# lv_controller_motor_drivers.net
KiCad netlist of a schematic drawn in Altium Designer
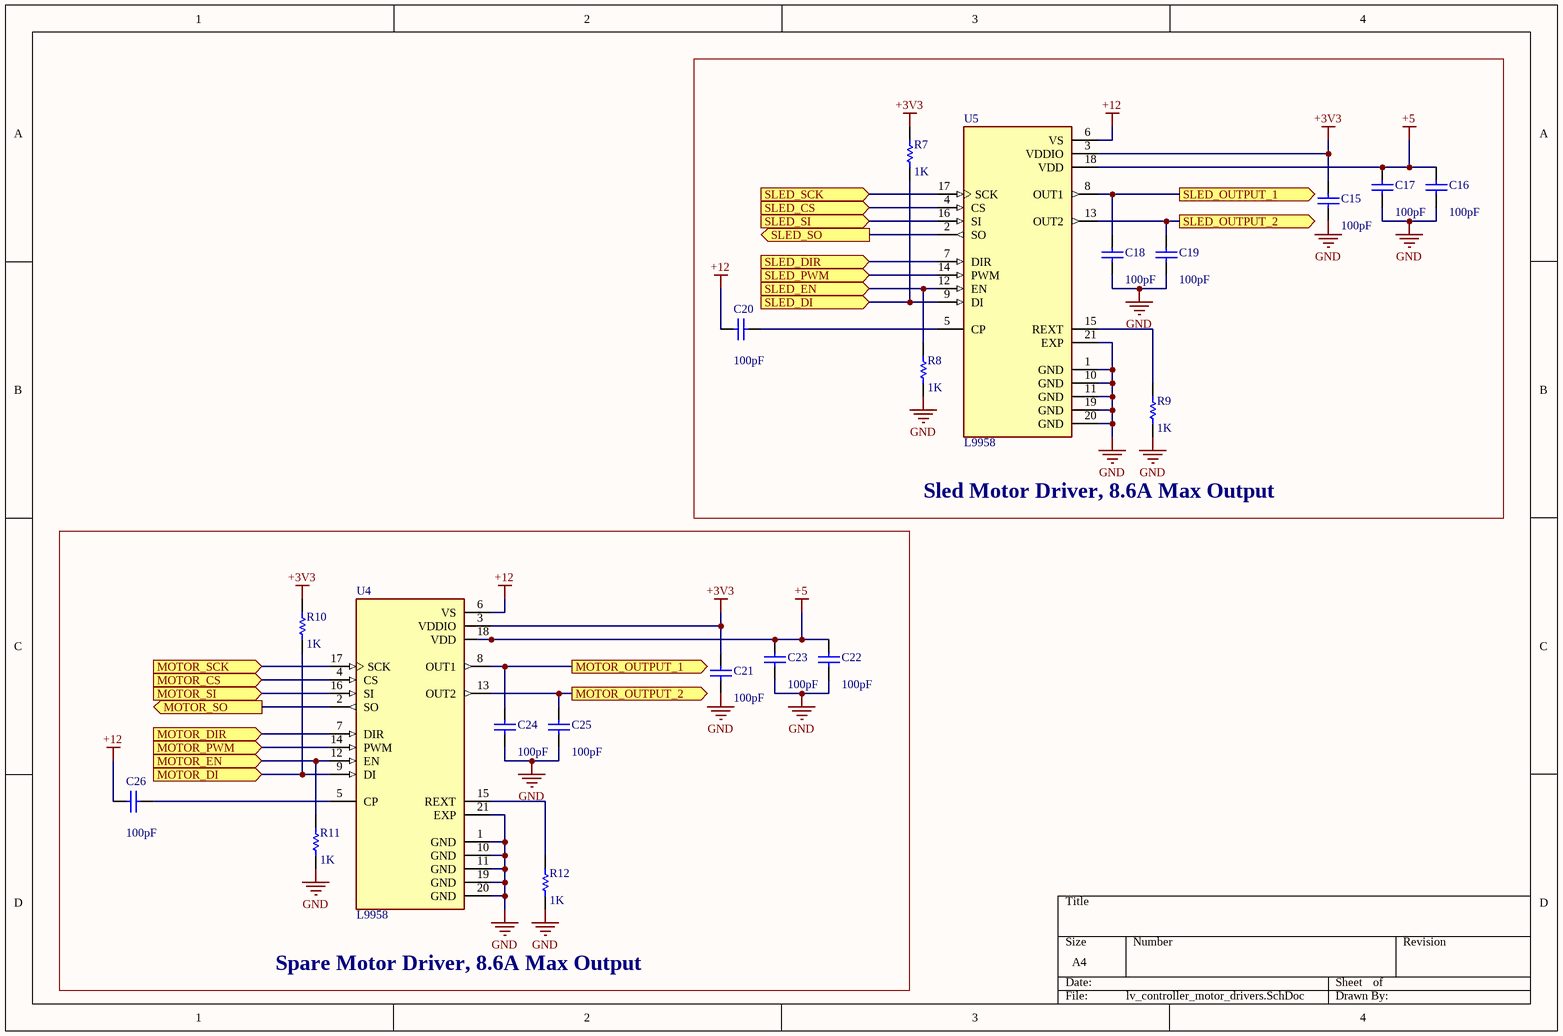
[diagram p0: lv_controller_motor_drivers.SchDoc]

(export (version "E")
  (design (tool "Eeschema 10.0.6"))
  (components
    (comp (ref "C15")
      (value "100pF")
      (footprint "C0805")
      (description "Capacitor")
      (fields (field (name "Comment") "Cap") (field (name "PUBLISHER") "Altium Limited"))
      (libsource (lib "Miscellaneous Devices") (part "Cap"))
    )
    (comp (ref "C16")
      (value "100pF")
      (footprint "C0805")
      (description "Capacitor")
      (fields (field (name "Comment") "Cap") (field (name "PUBLISHER") "Altium Limited"))
      (libsource (lib "Miscellaneous Devices") (part "Cap"))
    )
    (comp (ref "C17")
      (value "100pF")
      (footprint "C0805")
      (description "Capacitor")
      (fields (field (name "Comment") "Cap") (field (name "PUBLISHER") "Altium Limited"))
      (libsource (lib "Miscellaneous Devices") (part "Cap"))
    )
    (comp (ref "C18")
      (value "100pF")
      (footprint "C0805")
      (description "Capacitor")
      (fields (field (name "Comment") "Cap") (field (name "PUBLISHER") "Altium Limited"))
      (libsource (lib "Miscellaneous Devices") (part "Cap"))
    )
    (comp (ref "C19")
      (value "100pF")
      (footprint "C0805")
      (description "Capacitor")
      (fields (field (name "Comment") "Cap") (field (name "PUBLISHER") "Altium Limited"))
      (libsource (lib "Miscellaneous Devices") (part "Cap"))
    )
    (comp (ref "C20")
      (value "100pF")
      (footprint "C0805")
      (description "Capacitor")
      (fields (field (name "Comment") "Cap") (field (name "PUBLISHER") "Altium Limited"))
      (libsource (lib "Miscellaneous Devices") (part "Cap"))
    )
    (comp (ref "C21")
      (value "100pF")
      (footprint "C0805")
      (description "Capacitor")
      (fields (field (name "Comment") "Cap") (field (name "PUBLISHER") "Altium Limited"))
      (libsource (lib "Miscellaneous Devices") (part "Cap"))
    )
    (comp (ref "C22")
      (value "100pF")
      (footprint "C0805")
      (description "Capacitor")
      (fields (field (name "Comment") "Cap") (field (name "PUBLISHER") "Altium Limited"))
      (libsource (lib "Miscellaneous Devices") (part "Cap"))
    )
    (comp (ref "C23")
      (value "100pF")
      (footprint "C0805")
      (description "Capacitor")
      (fields (field (name "Comment") "Cap") (field (name "PUBLISHER") "Altium Limited"))
      (libsource (lib "Miscellaneous Devices") (part "Cap"))
    )
    (comp (ref "C24")
      (value "100pF")
      (footprint "C0805")
      (description "Capacitor")
      (fields (field (name "Comment") "Cap") (field (name "PUBLISHER") "Altium Limited"))
      (libsource (lib "Miscellaneous Devices") (part "Cap"))
    )
    (comp (ref "C25")
      (value "100pF")
      (footprint "C0805")
      (description "Capacitor")
      (fields (field (name "Comment") "Cap") (field (name "PUBLISHER") "Altium Limited"))
      (libsource (lib "Miscellaneous Devices") (part "Cap"))
    )
    (comp (ref "C26")
      (value "100pF")
      (footprint "C0805")
      (description "Capacitor")
      (fields (field (name "Comment") "Cap") (field (name "PUBLISHER") "Altium Limited"))
      (libsource (lib "Miscellaneous Devices") (part "Cap"))
    )
    (comp (ref "R7")
      (value "1K")
      (footprint "6-0805_M")
      (description "Resistor")
      (fields (field (name "Comment") "Res1") (field (name "PUBLISHER") "Altium Limited"))
      (libsource (lib "Miscellaneous Devices") (part "Res1"))
    )
    (comp (ref "R8")
      (value "1K")
      (footprint "6-0805_M")
      (description "Resistor")
      (fields (field (name "Comment") "Res1") (field (name "PUBLISHER") "Altium Limited"))
      (libsource (lib "Miscellaneous Devices") (part "Res1"))
    )
    (comp (ref "R9")
      (value "1K")
      (footprint "6-0805_M")
      (description "Resistor")
      (fields (field (name "Comment") "Res1") (field (name "PUBLISHER") "Altium Limited"))
      (libsource (lib "Miscellaneous Devices") (part "Res1"))
    )
    (comp (ref "R10")
      (value "1K")
      (footprint "6-0805_M")
      (description "Resistor")
      (fields (field (name "Comment") "Res1") (field (name "PUBLISHER") "Altium Limited"))
      (libsource (lib "Miscellaneous Devices") (part "Res1"))
    )
    (comp (ref "R11")
      (value "1K")
      (footprint "6-0805_M")
      (description "Resistor")
      (fields (field (name "Comment") "Res1") (field (name "PUBLISHER") "Altium Limited"))
      (libsource (lib "Miscellaneous Devices") (part "Res1"))
    )
    (comp (ref "R12")
      (value "1K")
      (footprint "6-0805_M")
      (description "Resistor")
      (fields (field (name "Comment") "Res1") (field (name "PUBLISHER") "Altium Limited"))
      (libsource (lib "Miscellaneous Devices") (part "Res1"))
    )
    (comp (ref "U4")
      (value "L9958")
      (footprint "SOIC127P1420X360-21N")
      (description "Bipolar Motor Driver CMOS SPI PowerSO-16â„¢")
      (fields (field (name "MF") "STMicroelectronics"))
      (libsource (lib "lv_controller_lib") (part "L9958"))
    )
    (comp (ref "U5")
      (value "L9958")
      (footprint "SOIC127P1420X360-21N")
      (description "Bipolar Motor Driver CMOS SPI PowerSO-16â„¢")
      (fields (field (name "MF") "STMicroelectronics"))
      (libsource (lib "lv_controller_lib") (part "L9958"))
    )
  )
  (nets
    (net (code "1") (name "+3V3") (class "Default")
      (node (ref "C15") (pin "2") (pinfunction "2_2") (pintype "passive"))
      (node (ref "C21") (pin "2") (pinfunction "2_2") (pintype "passive"))
      (node (ref "R10") (pin "1") (pinfunction "1_1") (pintype "passive"))
      (node (ref "R7") (pin "1") (pinfunction "1_1") (pintype "passive"))
      (node (ref "U4") (pin "3") (pinfunction "VDDIO_3") (pintype "power_in"))
      (node (ref "U5") (pin "3") (pinfunction "VDDIO_3") (pintype "power_in"))
    )
    (net (code "2") (name "+5") (class "Default")
      (node (ref "C16") (pin "2") (pinfunction "2_2") (pintype "passive"))
      (node (ref "C17") (pin "2") (pinfunction "2_2") (pintype "passive"))
      (node (ref "C22") (pin "2") (pinfunction "2_2") (pintype "passive"))
      (node (ref "C23") (pin "2") (pinfunction "2_2") (pintype "passive"))
      (node (ref "U4") (pin "18") (pinfunction "VDD_18") (pintype "power_in"))
      (node (ref "U5") (pin "18") (pinfunction "VDD_18") (pintype "power_in"))
    )
    (net (code "3") (name "+12") (class "Default")
      (node (ref "C20") (pin "1") (pinfunction "1_1") (pintype "passive"))
      (node (ref "C26") (pin "1") (pinfunction "1_1") (pintype "passive"))
      (node (ref "U4") (pin "6") (pinfunction "VS_6") (pintype "power_in"))
      (node (ref "U5") (pin "6") (pinfunction "VS_6") (pintype "power_in"))
    )
    (net (code "4") (name "/MOTOR_CS") (class "Default")
      (node (ref "U4") (pin "4") (pinfunction "CS_4") (pintype "input"))
    )
    (net (code "5") (name "/MOTOR_DI") (class "Default")
      (node (ref "R10") (pin "2") (pinfunction "2_2") (pintype "passive"))
      (node (ref "U4") (pin "9") (pinfunction "DI_9") (pintype "input"))
    )
    (net (code "6") (name "/MOTOR_DIR") (class "Default")
      (node (ref "U4") (pin "7") (pinfunction "DIR_7") (pintype "input"))
    )
    (net (code "7") (name "/MOTOR_EN") (class "Default")
      (node (ref "R11") (pin "1") (pinfunction "1_1") (pintype "passive"))
      (node (ref "U4") (pin "12") (pinfunction "EN_12") (pintype "input"))
    )
    (net (code "8") (name "/MOTOR_OUTPUT_1") (class "Default")
      (node (ref "C24") (pin "2") (pinfunction "2_2") (pintype "passive"))
      (node (ref "U4") (pin "8") (pinfunction "OUT1_8") (pintype "output"))
    )
    (net (code "9") (name "/MOTOR_OUTPUT_2") (class "Default")
      (node (ref "C25") (pin "2") (pinfunction "2_2") (pintype "passive"))
      (node (ref "U4") (pin "13") (pinfunction "OUT2_13") (pintype "output"))
    )
    (net (code "10") (name "/MOTOR_PWM") (class "Default")
      (node (ref "U4") (pin "14") (pinfunction "PWM_14") (pintype "input"))
    )
    (net (code "11") (name "/MOTOR_SCK") (class "Default")
      (node (ref "U4") (pin "17") (pinfunction "SCK_17") (pintype "input"))
    )
    (net (code "12") (name "/MOTOR_SI") (class "Default")
      (node (ref "U4") (pin "16") (pinfunction "SI_16") (pintype "input"))
    )
    (net (code "13") (name "/MOTOR_SO") (class "Default")
      (node (ref "U4") (pin "2") (pinfunction "SO_2") (pintype "output"))
    )
    (net (code "14") (name "/SLED_CS") (class "Default")
      (node (ref "U5") (pin "4") (pinfunction "CS_4") (pintype "input"))
    )
    (net (code "15") (name "/SLED_DI") (class "Default")
      (node (ref "R7") (pin "2") (pinfunction "2_2") (pintype "passive"))
      (node (ref "U5") (pin "9") (pinfunction "DI_9") (pintype "input"))
    )
    (net (code "16") (name "/SLED_DIR") (class "Default")
      (node (ref "U5") (pin "7") (pinfunction "DIR_7") (pintype "input"))
    )
    (net (code "17") (name "/SLED_EN") (class "Default")
      (node (ref "R8") (pin "1") (pinfunction "1_1") (pintype "passive"))
      (node (ref "U5") (pin "12") (pinfunction "EN_12") (pintype "input"))
    )
    (net (code "18") (name "/SLED_OUTPUT_1") (class "Default")
      (node (ref "C18") (pin "2") (pinfunction "2_2") (pintype "passive"))
      (node (ref "U5") (pin "8") (pinfunction "OUT1_8") (pintype "output"))
    )
    (net (code "19") (name "/SLED_OUTPUT_2") (class "Default")
      (node (ref "C19") (pin "2") (pinfunction "2_2") (pintype "passive"))
      (node (ref "U5") (pin "13") (pinfunction "OUT2_13") (pintype "output"))
    )
    (net (code "20") (name "/SLED_PWM") (class "Default")
      (node (ref "U5") (pin "14") (pinfunction "PWM_14") (pintype "input"))
    )
    (net (code "21") (name "/SLED_SCK") (class "Default")
      (node (ref "U5") (pin "17") (pinfunction "SCK_17") (pintype "input"))
    )
    (net (code "22") (name "/SLED_SI") (class "Default")
      (node (ref "U5") (pin "16") (pinfunction "SI_16") (pintype "input"))
    )
    (net (code "23") (name "/SLED_SO") (class "Default")
      (node (ref "U5") (pin "2") (pinfunction "SO_2") (pintype "output"))
    )
    (net (code "24") (name "GND") (class "Default")
      (node (ref "C15") (pin "1") (pinfunction "1_1") (pintype "passive"))
      (node (ref "C16") (pin "1") (pinfunction "1_1") (pintype "passive"))
      (node (ref "C17") (pin "1") (pinfunction "1_1") (pintype "passive"))
      (node (ref "C18") (pin "1") (pinfunction "1_1") (pintype "passive"))
      (node (ref "C19") (pin "1") (pinfunction "1_1") (pintype "passive"))
      (node (ref "C21") (pin "1") (pinfunction "1_1") (pintype "passive"))
      (node (ref "C22") (pin "1") (pinfunction "1_1") (pintype "passive"))
      (node (ref "C23") (pin "1") (pinfunction "1_1") (pintype "passive"))
      (node (ref "C24") (pin "1") (pinfunction "1_1") (pintype "passive"))
      (node (ref "C25") (pin "1") (pinfunction "1_1") (pintype "passive"))
      (node (ref "R11") (pin "2") (pinfunction "2_2") (pintype "passive"))
      (node (ref "R12") (pin "2") (pinfunction "2_2") (pintype "passive"))
      (node (ref "R8") (pin "2") (pinfunction "2_2") (pintype "passive"))
      (node (ref "R9") (pin "2") (pinfunction "2_2") (pintype "passive"))
      (node (ref "U4") (pin "1") (pinfunction "GND_1") (pintype "power_in"))
      (node (ref "U4") (pin "10") (pinfunction "GND_10") (pintype "power_in"))
      (node (ref "U4") (pin "11") (pinfunction "GND_11") (pintype "power_in"))
      (node (ref "U4") (pin "19") (pinfunction "GND_19") (pintype "power_in"))
      (node (ref "U4") (pin "20") (pinfunction "GND_20") (pintype "power_in"))
      (node (ref "U4") (pin "21") (pinfunction "EXP_21") (pintype "passive"))
      (node (ref "U5") (pin "1") (pinfunction "GND_1") (pintype "power_in"))
      (node (ref "U5") (pin "10") (pinfunction "GND_10") (pintype "power_in"))
      (node (ref "U5") (pin "11") (pinfunction "GND_11") (pintype "power_in"))
      (node (ref "U5") (pin "19") (pinfunction "GND_19") (pintype "power_in"))
      (node (ref "U5") (pin "20") (pinfunction "GND_20") (pintype "power_in"))
      (node (ref "U5") (pin "21") (pinfunction "EXP_21") (pintype "passive"))
    )
    (net (code "25") (name "Net-(U4-CP)") (class "Default")
      (node (ref "C26") (pin "2") (pinfunction "2_2") (pintype "passive"))
      (node (ref "U4") (pin "5") (pinfunction "CP_5") (pintype "passive"))
    )
    (net (code "26") (name "Net-(U4-REXT)") (class "Default")
      (node (ref "R12") (pin "1") (pinfunction "1_1") (pintype "passive"))
      (node (ref "U4") (pin "15") (pinfunction "REXT_15") (pintype "passive"))
    )
    (net (code "27") (name "Net-(U5-CP)") (class "Default")
      (node (ref "C20") (pin "2") (pinfunction "2_2") (pintype "passive"))
      (node (ref "U5") (pin "5") (pinfunction "CP_5") (pintype "passive"))
    )
    (net (code "28") (name "Net-(U5-REXT)") (class "Default")
      (node (ref "R9") (pin "1") (pinfunction "1_1") (pintype "passive"))
      (node (ref "U5") (pin "15") (pinfunction "REXT_15") (pintype "passive"))
    )
  )
)
